# Board_OLED.net
KiCad netlist of a schematic drawn in EAGLE
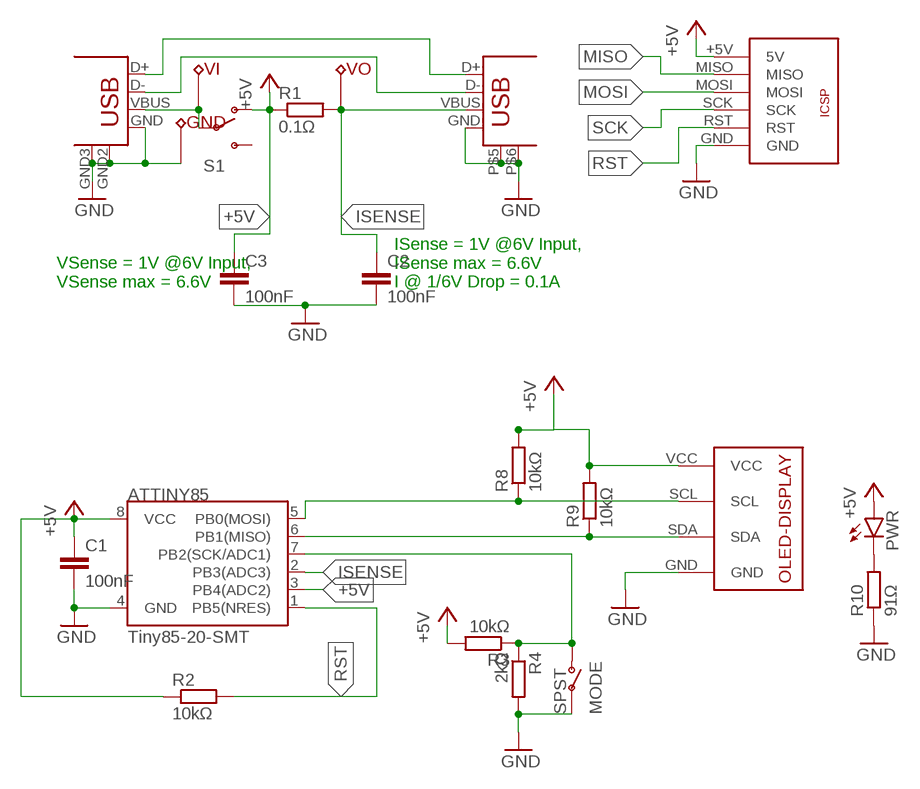
[diagram p0: schematic, sheet 1]

(export (version "E")
  (design (tool "Eeschema 10.0.6"))
  (components
    (comp (ref "ATTINY85")
      (value "Tiny85-20-SMT")
      (footprint "eagle-import:SO08-EIAJ")
      (libsource (lib "eagle-import") (part "ATTINY45TINY85-20-SMT"))
    )
    (comp (ref "C1")
      (value "100nF")
      (footprint "eagle-import:C0603")
      (libsource (lib "eagle-import") (part "C-EUC0603"))
    )
    (comp (ref "C2")
      (value "100nF")
      (footprint "eagle-import:C0603")
      (libsource (lib "eagle-import") (part "C-EUC0603"))
    )
    (comp (ref "C3")
      (value "100nF")
      (footprint "eagle-import:C0603")
      (libsource (lib "eagle-import") (part "C-EUC0603"))
    )
    (comp (ref "GND")
      (value "TESTPOINT0.5MM-DRILL-WIRE-LOOP")
      (footprint "eagle-import:TP-0.5MM-DUAL")
      (libsource (lib "eagle-import") (part "TESTPOINT0.5MM-DRILL-WIRE-LOOP"))
    )
    (comp (ref "INPUT")
      (value "USB+SHIELDTHROUGHHOLE-MALE")
      (footprint "eagle-import:USB-A-H")
      (libsource (lib "eagle-import") (part "USB+SHIELDTHROUGHHOLE-MALE"))
    )
    (comp (ref "MODE")
      (value "SPST")
      (footprint "eagle-import:WUERTH-SPST-SMD")
      (libsource (lib "eagle-import") (part "SPST"))
    )
    (comp (ref "OUTPUT")
      (value "USB+SHIELDTHROUGHOLE-FEMALE")
      (footprint "eagle-import:USB-A-S-SILK-THROUGHHOLE")
      (libsource (lib "eagle-import") (part "USB+SHIELDTHROUGHOLE-FEMALE"))
    )
    (comp (ref "PWR")
      (value "LED0603")
      (footprint "eagle-import:LED-0603")
      (libsource (lib "eagle-import") (part "LED0603"))
    )
    (comp (ref "R1")
      (value "0.1Ω")
      (footprint "eagle-import:R2512")
      (libsource (lib "eagle-import") (part "R-EU_R2512"))
    )
    (comp (ref "R2")
      (value "10kΩ")
      (footprint "eagle-import:R0603")
      (libsource (lib "eagle-import") (part "R-EU_R0603"))
    )
    (comp (ref "R3")
      (value "10kΩ")
      (footprint "eagle-import:R0603")
      (libsource (lib "eagle-import") (part "R-EU_R0603"))
    )
    (comp (ref "R4")
      (value "2kΩ")
      (footprint "eagle-import:R0603")
      (libsource (lib "eagle-import") (part "R-EU_R0603"))
    )
    (comp (ref "R8")
      (value "10kΩ")
      (footprint "eagle-import:R0603")
      (libsource (lib "eagle-import") (part "R-EU_R0603"))
    )
    (comp (ref "R9")
      (value "10kΩ")
      (footprint "eagle-import:R0603")
      (libsource (lib "eagle-import") (part "R-EU_R0603"))
    )
    (comp (ref "R10")
      (value "91Ω")
      (footprint "eagle-import:R0603")
      (libsource (lib "eagle-import") (part "R-EU_R0603"))
    )
    (comp (ref "S1")
      (value "SWITCH-SPDT-SMD-A")
      (footprint "eagle-import:SWITCH-SPST-SMD-A")
      (libsource (lib "eagle-import") (part "SWITCH-SPDT-SMD-A"))
    )
    (comp (ref "U$1")
      (value "ICSPSMD")
      (footprint "eagle-import:ICSP-SMD")
      (libsource (lib "eagle-import") (part "ICSPSMD"))
    )
    (comp (ref "U$2")
      (value "OLED-I2C")
      (footprint "eagle-import:OLED-I2C")
      (libsource (lib "eagle-import") (part "OLED-I2C"))
    )
    (comp (ref "VI")
      (value "TESTPOINT0.5MM-DRILL-WIRE-LOOP")
      (footprint "eagle-import:TP-0.5MM-DUAL")
      (libsource (lib "eagle-import") (part "TESTPOINT0.5MM-DRILL-WIRE-LOOP"))
    )
    (comp (ref "VO")
      (value "TESTPOINT0.5MM-DRILL-WIRE-LOOP")
      (footprint "eagle-import:TP-0.5MM-DUAL")
      (libsource (lib "eagle-import") (part "TESTPOINT0.5MM-DRILL-WIRE-LOOP"))
    )
  )
  (nets
    (net (code "1") (name "+5V") (class "Default")
      (node (ref "ATTINY85") (pin "3") (pinfunction "PB4(ADC2)_3") (pintype "bidirectional"))
      (node (ref "ATTINY85") (pin "8") (pinfunction "VCC_8") (pintype "bidirectional"))
      (node (ref "C1") (pin "1") (pinfunction "1_1") (pintype "passive"))
      (node (ref "C3") (pin "1") (pinfunction "1_1") (pintype "passive"))
      (node (ref "PWR") (pin "A") (pinfunction "A_A") (pintype "passive"))
      (node (ref "R1") (pin "1") (pinfunction "1_1") (pintype "passive"))
      (node (ref "R2") (pin "1") (pinfunction "1_1") (pintype "passive"))
      (node (ref "R3") (pin "2") (pinfunction "2_2") (pintype "passive"))
      (node (ref "R8") (pin "2") (pinfunction "2_2") (pintype "passive"))
      (node (ref "R9") (pin "2") (pinfunction "2_2") (pintype "passive"))
      (node (ref "S1") (pin "1") (pinfunction "O_1") (pintype "passive"))
      (node (ref "U$1") (pin "+5V") (pinfunction "5V_+5V") (pintype "bidirectional"))
      (node (ref "U$2") (pin "VCC") (pinfunction "VCC_VCC") (pintype "bidirectional"))
    )
    (net (code "2") (name "GND") (class "Default")
      (node (ref "ATTINY85") (pin "4") (pinfunction "GND_4") (pintype "bidirectional"))
      (node (ref "C1") (pin "2") (pinfunction "2_2") (pintype "passive"))
      (node (ref "C2") (pin "2") (pinfunction "2_2") (pintype "passive"))
      (node (ref "C3") (pin "2") (pinfunction "2_2") (pintype "passive"))
      (node (ref "GND") (pin "P$1") (pinfunction "TP_P$1") (pintype "bidirectional"))
      (node (ref "GND") (pin "P$2") (pinfunction "TP_P$2") (pintype "bidirectional"))
      (node (ref "INPUT") (pin "GND") (pinfunction "GND_GND") (pintype "bidirectional"))
      (node (ref "INPUT") (pin "GND2") (pinfunction "S1_GND2") (pintype "bidirectional"))
      (node (ref "INPUT") (pin "GND3") (pinfunction "S2_GND3") (pintype "bidirectional"))
      (node (ref "MODE") (pin "1") (pinfunction "P_1") (pintype "passive"))
      (node (ref "MODE") (pin "3") (pinfunction "P_3") (pintype "passive"))
      (node (ref "OUTPUT") (pin "GND") (pinfunction "GND_GND") (pintype "bidirectional"))
      (node (ref "OUTPUT") (pin "P$5") (pinfunction "S1_P$5") (pintype "bidirectional"))
      (node (ref "OUTPUT") (pin "P$6") (pinfunction "S2_P$6") (pintype "bidirectional"))
      (node (ref "R10") (pin "1") (pinfunction "1_1") (pintype "passive"))
      (node (ref "R4") (pin "2") (pinfunction "2_2") (pintype "passive"))
      (node (ref "U$1") (pin "GND") (pinfunction "GND_GND") (pintype "bidirectional"))
      (node (ref "U$2") (pin "GND") (pinfunction "GND_GND") (pintype "bidirectional"))
    )
    (net (code "3") (name "ISENSE") (class "Default")
      (node (ref "ATTINY85") (pin "2") (pinfunction "PB3(ADC3)_2") (pintype "bidirectional"))
      (node (ref "C2") (pin "1") (pinfunction "1_1") (pintype "passive"))
      (node (ref "OUTPUT") (pin "VBUS") (pinfunction "VBUS_VBUS") (pintype "bidirectional"))
      (node (ref "R1") (pin "2") (pinfunction "2_2") (pintype "passive"))
      (node (ref "VO") (pin "P$1") (pinfunction "TP_P$1") (pintype "bidirectional"))
      (node (ref "VO") (pin "P$2") (pinfunction "TP_P$2") (pintype "bidirectional"))
    )
    (net (code "4") (name "MISO") (class "Default")
      (node (ref "ATTINY85") (pin "6") (pinfunction "PB1(MISO)_6") (pintype "bidirectional"))
      (node (ref "R9") (pin "1") (pinfunction "1_1") (pintype "passive"))
      (node (ref "U$1") (pin "MISO") (pinfunction "MISO_MISO") (pintype "bidirectional"))
      (node (ref "U$2") (pin "SDA") (pinfunction "SDA_SDA") (pintype "bidirectional"))
    )
    (net (code "5") (name "MOSI") (class "Default")
      (node (ref "ATTINY85") (pin "5") (pinfunction "PB0(MOSI)_5") (pintype "bidirectional"))
      (node (ref "R8") (pin "1") (pinfunction "1_1") (pintype "passive"))
      (node (ref "U$1") (pin "MOSI") (pinfunction "MOSI_MOSI") (pintype "bidirectional"))
      (node (ref "U$2") (pin "SCL") (pinfunction "SCL_SCL") (pintype "bidirectional"))
    )
    (net (code "6") (name "Net-(INPUT-PadD+)") (class "Default")
      (node (ref "INPUT") (pin "D+") (pinfunction "D+_D+") (pintype "bidirectional"))
      (node (ref "OUTPUT") (pin "D+") (pinfunction "D+_D+") (pintype "bidirectional"))
    )
    (net (code "7") (name "Net-(INPUT-PadD-)") (class "Default")
      (node (ref "INPUT") (pin "D-") (pinfunction "D-_D-") (pintype "bidirectional"))
      (node (ref "OUTPUT") (pin "D-") (pinfunction "D-_D-") (pintype "bidirectional"))
    )
    (net (code "8") (name "Net-(PWR-PadC)") (class "Default")
      (node (ref "PWR") (pin "C") (pinfunction "C_C") (pintype "passive"))
      (node (ref "R10") (pin "2") (pinfunction "2_2") (pintype "passive"))
    )
    (net (code "9") (name "Net-(S1-P)") (class "Default")
      (node (ref "INPUT") (pin "VBUS") (pinfunction "VBUS_VBUS") (pintype "bidirectional"))
      (node (ref "S1") (pin "2") (pinfunction "P_2") (pintype "passive"))
      (node (ref "VI") (pin "P$1") (pinfunction "TP_P$1") (pintype "bidirectional"))
      (node (ref "VI") (pin "P$2") (pinfunction "TP_P$2") (pintype "bidirectional"))
    )
    (net (code "10") (name "RST") (class "Default")
      (node (ref "ATTINY85") (pin "1") (pinfunction "PB5(NRES)_1") (pintype "bidirectional"))
      (node (ref "R2") (pin "2") (pinfunction "2_2") (pintype "passive"))
      (node (ref "U$1") (pin "RST") (pinfunction "RST_RST") (pintype "bidirectional"))
    )
    (net (code "11") (name "SCK") (class "Default")
      (node (ref "ATTINY85") (pin "7") (pinfunction "PB2(SCK/ADC1)_7") (pintype "bidirectional"))
      (node (ref "MODE") (pin "2") (pinfunction "O_2") (pintype "passive"))
      (node (ref "MODE") (pin "4") (pinfunction "O_4") (pintype "passive"))
      (node (ref "R3") (pin "1") (pinfunction "1_1") (pintype "passive"))
      (node (ref "R4") (pin "1") (pinfunction "1_1") (pintype "passive"))
      (node (ref "U$1") (pin "SCK") (pinfunction "SCK_SCK") (pintype "bidirectional"))
    )
    (net (code "12") (name "unconnected-(S1-S-Pad3)") (class "Default")
      (node (ref "S1") (pin "3") (pinfunction "S_3") (pintype "passive"))
    )
  )
)
